# Ferdinand16.net
KiCad netlist of a schematic drawn in EAGLE
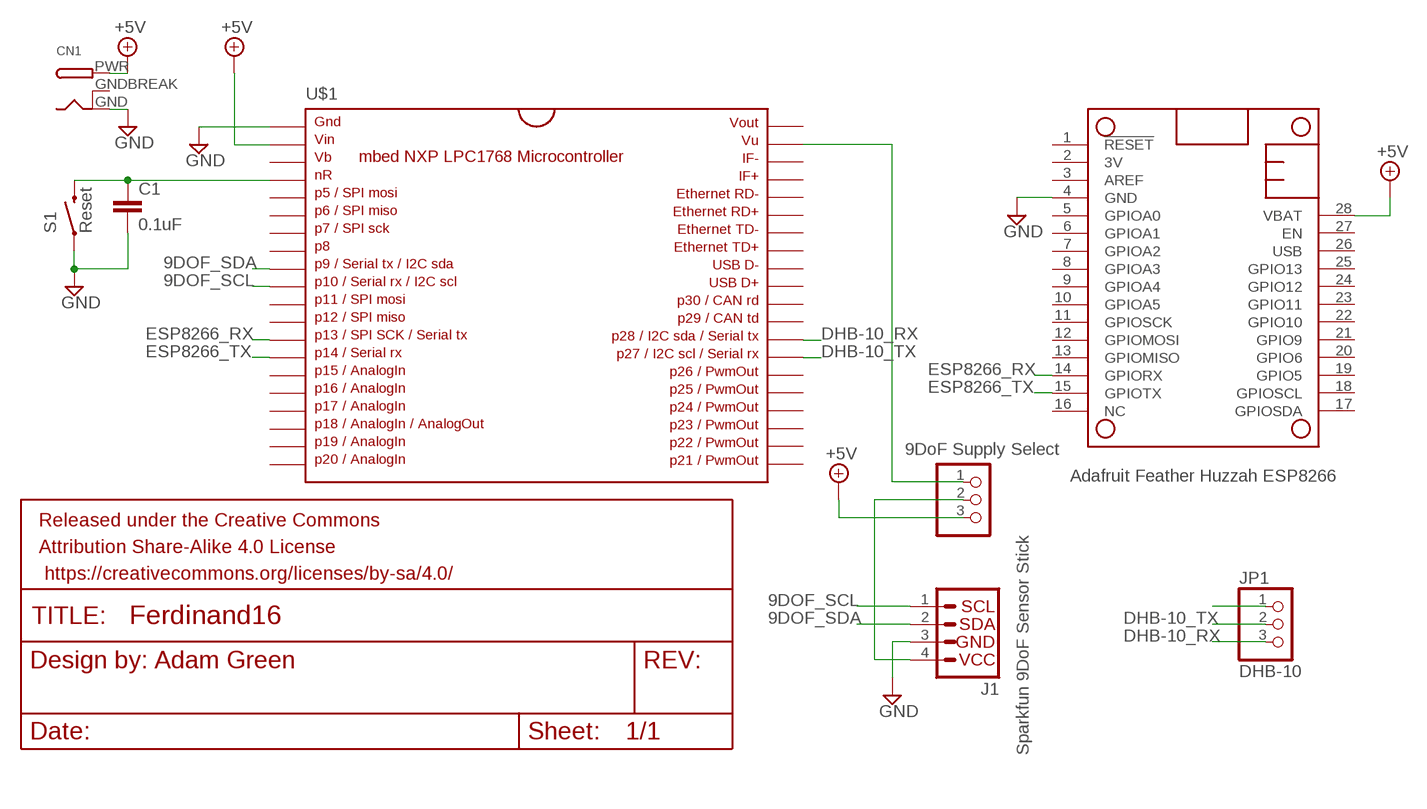
[diagram p0: schematic, sheet 1]

(export (version "E")
  (design (tool "Eeschema 10.0.6"))
  (components
    (comp (ref "C1")
      (value "0.1uF")
      (footprint "eagle-import:CAP-PTH-SMALL-KIT")
      (libsource (lib "eagle-import") (part "0.1UF-50V-20%(PTH)KIT-EZ"))
    )
    (comp (ref "CN1")
      (value "DCBARRELPTH")
      (footprint "eagle-import:DCJACK_2MM_PTH")
      (libsource (lib "eagle-import") (part "DCBARRELPTH"))
    )
    (comp (ref "J1")
      (value "Sparkfun 9DoF Sensor Stick")
      (footprint "eagle-import:1X04")
      (libsource (lib "eagle-import") (part "9DOF_SENSOR_STICK"))
    )
    (comp (ref "JP1")
      (value "DHB-10")
      (footprint "eagle-import:1X03_90")
      (libsource (lib "eagle-import") (part "PINHD-1X3/90"))
    )
    (comp (ref "JP2")
      (value "9DoF Supply Select")
      (footprint "eagle-import:1X03_90")
      (libsource (lib "eagle-import") (part "PINHD-1X3/90"))
    )
    (comp (ref "MS1")
      (value "FEATHERWING")
      (footprint "eagle-import:FEATHERWING")
      (libsource (lib "eagle-import") (part "FEATHERWING"))
    )
    (comp (ref "S1")
      (value "Reset")
      (footprint "eagle-import:TACTILE-PTH")
      (libsource (lib "eagle-import") (part "SWITCH-MOMENTARY-2PTH"))
    )
    (comp (ref "U$1")
      (value "MBED_NXP_LPC1768")
      (footprint "eagle-import:DIL40_0.9")
      (libsource (lib "eagle-import") (part "MBED_NXP_LPC1768"))
    )
  )
  (nets
    (net (code "1") (name "+5V") (class "Default")
      (node (ref "CN1") (pin "PWR") (pinfunction "PWR_PWR") (pintype "power_in"))
      (node (ref "JP2") (pin "3") (pinfunction "3_3") (pintype "passive"))
      (node (ref "MS1") (pin "28") (pinfunction "VBAT_28") (pintype "power_in"))
      (node (ref "U$1") (pin "2") (pinfunction "P$2_2") (pintype "bidirectional"))
    )
    (net (code "2") (name "/3V") (class "Default")
      (node (ref "MS1") (pin "2") (pinfunction "3V_2") (pintype "power_in"))
    )
    (net (code "3") (name "/9DOF_SCL") (class "Default")
      (node (ref "J1") (pin "1") (pinfunction "1_1") (pintype "passive"))
      (node (ref "U$1") (pin "10") (pinfunction "P$10_10") (pintype "bidirectional"))
    )
    (net (code "4") (name "/9DOF_SDA") (class "Default")
      (node (ref "J1") (pin "2") (pinfunction "2_2") (pintype "passive"))
      (node (ref "U$1") (pin "9") (pinfunction "P$9_9") (pintype "bidirectional"))
    )
    (net (code "5") (name "/DHB-10_RX") (class "Default")
      (node (ref "JP1") (pin "3") (pinfunction "3_3") (pintype "passive"))
      (node (ref "U$1") (pin "28") (pinfunction "P$28_28") (pintype "bidirectional"))
    )
    (net (code "6") (name "/DHB-10_TX") (class "Default")
      (node (ref "JP1") (pin "2") (pinfunction "2_2") (pintype "passive"))
      (node (ref "U$1") (pin "27") (pinfunction "P$27_27") (pintype "bidirectional"))
    )
    (net (code "7") (name "/ESP8266_RX") (class "Default")
      (node (ref "MS1") (pin "14") (pinfunction "GPIORX_14") (pintype "bidirectional"))
      (node (ref "U$1") (pin "13") (pinfunction "P$13_13") (pintype "bidirectional"))
    )
    (net (code "8") (name "/ESP8266_TX") (class "Default")
      (node (ref "MS1") (pin "15") (pinfunction "GPIOTX_15") (pintype "bidirectional"))
      (node (ref "U$1") (pin "14") (pinfunction "P$14_14") (pintype "bidirectional"))
    )
    (net (code "9") (name "/GNDBREAK") (class "Default")
      (node (ref "CN1") (pin "GNDBREAK") (pinfunction "GNDBREAK_GNDBREAK") (pintype "power_in"))
    )
    (net (code "10") (name "/USB") (class "Default")
      (node (ref "MS1") (pin "26") (pinfunction "USB_26") (pintype "power_in"))
    )
    (net (code "11") (name "GND") (class "Default")
      (node (ref "C1") (pin "2") (pinfunction "2_2") (pintype "passive"))
      (node (ref "CN1") (pin "GND") (pinfunction "GND_GND") (pintype "power_in"))
      (node (ref "J1") (pin "3") (pinfunction "3_3") (pintype "passive"))
      (node (ref "MS1") (pin "4") (pinfunction "GND_4") (pintype "power_in"))
      (node (ref "S1") (pin "1") (pinfunction "1_1") (pintype "passive"))
      (node (ref "U$1") (pin "1") (pinfunction "P$1_1") (pintype "bidirectional"))
    )
    (net (code "12") (name "Net-(J1-Pad4)") (class "Default")
      (node (ref "J1") (pin "4") (pinfunction "4_4") (pintype "passive"))
      (node (ref "JP2") (pin "2") (pinfunction "2_2") (pintype "passive"))
    )
    (net (code "13") (name "Net-(S1-2)") (class "Default")
      (node (ref "C1") (pin "1") (pinfunction "1_1") (pintype "passive"))
      (node (ref "S1") (pin "3") (pinfunction "2_3") (pintype "passive"))
      (node (ref "U$1") (pin "4") (pinfunction "P$4_4") (pintype "bidirectional"))
    )
    (net (code "14") (name "Net-(U$1-P$39)") (class "Default")
      (node (ref "JP2") (pin "1") (pinfunction "1_1") (pintype "passive"))
      (node (ref "U$1") (pin "39") (pinfunction "P$39_39") (pintype "bidirectional"))
    )
    (net (code "15") (name "unconnected-(JP1-Pad1)") (class "Default")
      (node (ref "JP1") (pin "1") (pinfunction "1_1") (pintype "passive"))
    )
    (net (code "16") (name "unconnected-(MS1-AREF-Pad3)") (class "Default")
      (node (ref "MS1") (pin "3") (pinfunction "AREF_3") (pintype "passive"))
    )
    (net (code "17") (name "unconnected-(MS1-EN-Pad27)") (class "Default")
      (node (ref "MS1") (pin "27") (pinfunction "EN_27") (pintype "passive"))
    )
    (net (code "18") (name "unconnected-(MS1-GPIO5-Pad19)") (class "Default")
      (node (ref "MS1") (pin "19") (pinfunction "GPIO5_19") (pintype "bidirectional"))
    )
    (net (code "19") (name "unconnected-(MS1-GPIO6-Pad20)") (class "Default")
      (node (ref "MS1") (pin "20") (pinfunction "GPIO6_20") (pintype "bidirectional"))
    )
    (net (code "20") (name "unconnected-(MS1-GPIO9-Pad21)") (class "Default")
      (node (ref "MS1") (pin "21") (pinfunction "GPIO9_21") (pintype "bidirectional"))
    )
    (net (code "21") (name "unconnected-(MS1-GPIO10-Pad22)") (class "Default")
      (node (ref "MS1") (pin "22") (pinfunction "GPIO10_22") (pintype "bidirectional"))
    )
    (net (code "22") (name "unconnected-(MS1-GPIO11-Pad23)") (class "Default")
      (node (ref "MS1") (pin "23") (pinfunction "GPIO11_23") (pintype "bidirectional"))
    )
    (net (code "23") (name "unconnected-(MS1-GPIO12-Pad24)") (class "Default")
      (node (ref "MS1") (pin "24") (pinfunction "GPIO12_24") (pintype "bidirectional"))
    )
    (net (code "24") (name "unconnected-(MS1-GPIO13-Pad25)") (class "Default")
      (node (ref "MS1") (pin "25") (pinfunction "GPIO13_25") (pintype "bidirectional"))
    )
    (net (code "25") (name "unconnected-(MS1-GPIOA0-Pad5)") (class "Default")
      (node (ref "MS1") (pin "5") (pinfunction "GPIOA0_5") (pintype "bidirectional"))
    )
    (net (code "26") (name "unconnected-(MS1-GPIOA1-Pad6)") (class "Default")
      (node (ref "MS1") (pin "6") (pinfunction "GPIOA1_6") (pintype "bidirectional"))
    )
    (net (code "27") (name "unconnected-(MS1-GPIOA2-Pad7)") (class "Default")
      (node (ref "MS1") (pin "7") (pinfunction "GPIOA2_7") (pintype "bidirectional"))
    )
    (net (code "28") (name "unconnected-(MS1-GPIOA3-Pad8)") (class "Default")
      (node (ref "MS1") (pin "8") (pinfunction "GPIOA3_8") (pintype "bidirectional"))
    )
    (net (code "29") (name "unconnected-(MS1-GPIOA4-Pad9)") (class "Default")
      (node (ref "MS1") (pin "9") (pinfunction "GPIOA4_9") (pintype "bidirectional"))
    )
    (net (code "30") (name "unconnected-(MS1-GPIOA5-Pad10)") (class "Default")
      (node (ref "MS1") (pin "10") (pinfunction "GPIOA5_10") (pintype "bidirectional"))
    )
    (net (code "31") (name "unconnected-(MS1-GPIOMISO-Pad13)") (class "Default")
      (node (ref "MS1") (pin "13") (pinfunction "GPIOMISO_13") (pintype "bidirectional"))
    )
    (net (code "32") (name "unconnected-(MS1-GPIOMOSI-Pad12)") (class "Default")
      (node (ref "MS1") (pin "12") (pinfunction "GPIOMOSI_12") (pintype "bidirectional"))
    )
    (net (code "33") (name "unconnected-(MS1-GPIOSCK-Pad11)") (class "Default")
      (node (ref "MS1") (pin "11") (pinfunction "GPIOSCK_11") (pintype "bidirectional"))
    )
    (net (code "34") (name "unconnected-(MS1-GPIOSCL-Pad18)") (class "Default")
      (node (ref "MS1") (pin "18") (pinfunction "GPIOSCL_18") (pintype "bidirectional"))
    )
    (net (code "35") (name "unconnected-(MS1-GPIOSDA-Pad17)") (class "Default")
      (node (ref "MS1") (pin "17") (pinfunction "GPIOSDA_17") (pintype "bidirectional"))
    )
    (net (code "36") (name "unconnected-(MS1-NC-Pad16)") (class "Default")
      (node (ref "MS1") (pin "16") (pinfunction "NC_16") (pintype "passive"))
    )
    (net (code "37") (name "unconnected-(MS1-~{RESET}-Pad1)") (class "Default")
      (node (ref "MS1") (pin "1") (pinfunction "~{RESET}_1") (pintype "input"))
    )
    (net (code "38") (name "unconnected-(U$1-P$3-Pad3)") (class "Default")
      (node (ref "U$1") (pin "3") (pinfunction "P$3_3") (pintype "bidirectional"))
    )
    (net (code "39") (name "unconnected-(U$1-P$5-Pad5)") (class "Default")
      (node (ref "U$1") (pin "5") (pinfunction "P$5_5") (pintype "bidirectional"))
    )
    (net (code "40") (name "unconnected-(U$1-P$6-Pad6)") (class "Default")
      (node (ref "U$1") (pin "6") (pinfunction "P$6_6") (pintype "bidirectional"))
    )
    (net (code "41") (name "unconnected-(U$1-P$7-Pad7)") (class "Default")
      (node (ref "U$1") (pin "7") (pinfunction "P$7_7") (pintype "bidirectional"))
    )
    (net (code "42") (name "unconnected-(U$1-P$8-Pad8)") (class "Default")
      (node (ref "U$1") (pin "8") (pinfunction "P$8_8") (pintype "bidirectional"))
    )
    (net (code "43") (name "unconnected-(U$1-P$11-Pad11)") (class "Default")
      (node (ref "U$1") (pin "11") (pinfunction "P$11_11") (pintype "bidirectional"))
    )
    (net (code "44") (name "unconnected-(U$1-P$12-Pad12)") (class "Default")
      (node (ref "U$1") (pin "12") (pinfunction "P$12_12") (pintype "bidirectional"))
    )
    (net (code "45") (name "unconnected-(U$1-P$15-Pad15)") (class "Default")
      (node (ref "U$1") (pin "15") (pinfunction "P$15_15") (pintype "bidirectional"))
    )
    (net (code "46") (name "unconnected-(U$1-P$16-Pad16)") (class "Default")
      (node (ref "U$1") (pin "16") (pinfunction "P$16_16") (pintype "bidirectional"))
    )
    (net (code "47") (name "unconnected-(U$1-P$17-Pad17)") (class "Default")
      (node (ref "U$1") (pin "17") (pinfunction "P$17_17") (pintype "bidirectional"))
    )
    (net (code "48") (name "unconnected-(U$1-P$18-Pad18)") (class "Default")
      (node (ref "U$1") (pin "18") (pinfunction "P$18_18") (pintype "bidirectional"))
    )
    (net (code "49") (name "unconnected-(U$1-P$19-Pad19)") (class "Default")
      (node (ref "U$1") (pin "19") (pinfunction "P$19_19") (pintype "bidirectional"))
    )
    (net (code "50") (name "unconnected-(U$1-P$20-Pad20)") (class "Default")
      (node (ref "U$1") (pin "20") (pinfunction "P$20_20") (pintype "bidirectional"))
    )
    (net (code "51") (name "unconnected-(U$1-P$21-Pad21)") (class "Default")
      (node (ref "U$1") (pin "21") (pinfunction "P$21_21") (pintype "bidirectional"))
    )
    (net (code "52") (name "unconnected-(U$1-P$22-Pad22)") (class "Default")
      (node (ref "U$1") (pin "22") (pinfunction "P$22_22") (pintype "bidirectional"))
    )
    (net (code "53") (name "unconnected-(U$1-P$23-Pad23)") (class "Default")
      (node (ref "U$1") (pin "23") (pinfunction "P$23_23") (pintype "bidirectional"))
    )
    (net (code "54") (name "unconnected-(U$1-P$24-Pad24)") (class "Default")
      (node (ref "U$1") (pin "24") (pinfunction "P$24_24") (pintype "bidirectional"))
    )
    (net (code "55") (name "unconnected-(U$1-P$25-Pad25)") (class "Default")
      (node (ref "U$1") (pin "25") (pinfunction "P$25_25") (pintype "bidirectional"))
    )
    (net (code "56") (name "unconnected-(U$1-P$26-Pad26)") (class "Default")
      (node (ref "U$1") (pin "26") (pinfunction "P$26_26") (pintype "bidirectional"))
    )
    (net (code "57") (name "unconnected-(U$1-P$29-Pad29)") (class "Default")
      (node (ref "U$1") (pin "29") (pinfunction "P$29_29") (pintype "bidirectional"))
    )
    (net (code "58") (name "unconnected-(U$1-P$30-Pad30)") (class "Default")
      (node (ref "U$1") (pin "30") (pinfunction "P$30_30") (pintype "bidirectional"))
    )
    (net (code "59") (name "unconnected-(U$1-P$31-Pad31)") (class "Default")
      (node (ref "U$1") (pin "31") (pinfunction "P$31_31") (pintype "bidirectional"))
    )
    (net (code "60") (name "unconnected-(U$1-P$32-Pad32)") (class "Default")
      (node (ref "U$1") (pin "32") (pinfunction "P$32_32") (pintype "bidirectional"))
    )
    (net (code "61") (name "unconnected-(U$1-P$33-Pad33)") (class "Default")
      (node (ref "U$1") (pin "33") (pinfunction "P$33_33") (pintype "bidirectional"))
    )
    (net (code "62") (name "unconnected-(U$1-P$34-Pad34)") (class "Default")
      (node (ref "U$1") (pin "34") (pinfunction "P$34_34") (pintype "bidirectional"))
    )
    (net (code "63") (name "unconnected-(U$1-P$35-Pad35)") (class "Default")
      (node (ref "U$1") (pin "35") (pinfunction "P$35_35") (pintype "bidirectional"))
    )
    (net (code "64") (name "unconnected-(U$1-P$36-Pad36)") (class "Default")
      (node (ref "U$1") (pin "36") (pinfunction "P$36_36") (pintype "bidirectional"))
    )
    (net (code "65") (name "unconnected-(U$1-P$37-Pad37)") (class "Default")
      (node (ref "U$1") (pin "37") (pinfunction "P$37_37") (pintype "bidirectional"))
    )
    (net (code "66") (name "unconnected-(U$1-P$38-Pad38)") (class "Default")
      (node (ref "U$1") (pin "38") (pinfunction "P$38_38") (pintype "bidirectional"))
    )
    (net (code "67") (name "unconnected-(U$1-P$40-Pad40)") (class "Default")
      (node (ref "U$1") (pin "40") (pinfunction "P$40_40") (pintype "bidirectional"))
    )
  )
)
